# E17-04_BSPD.net
KiCad netlist of a schematic drawn in Altium Designer
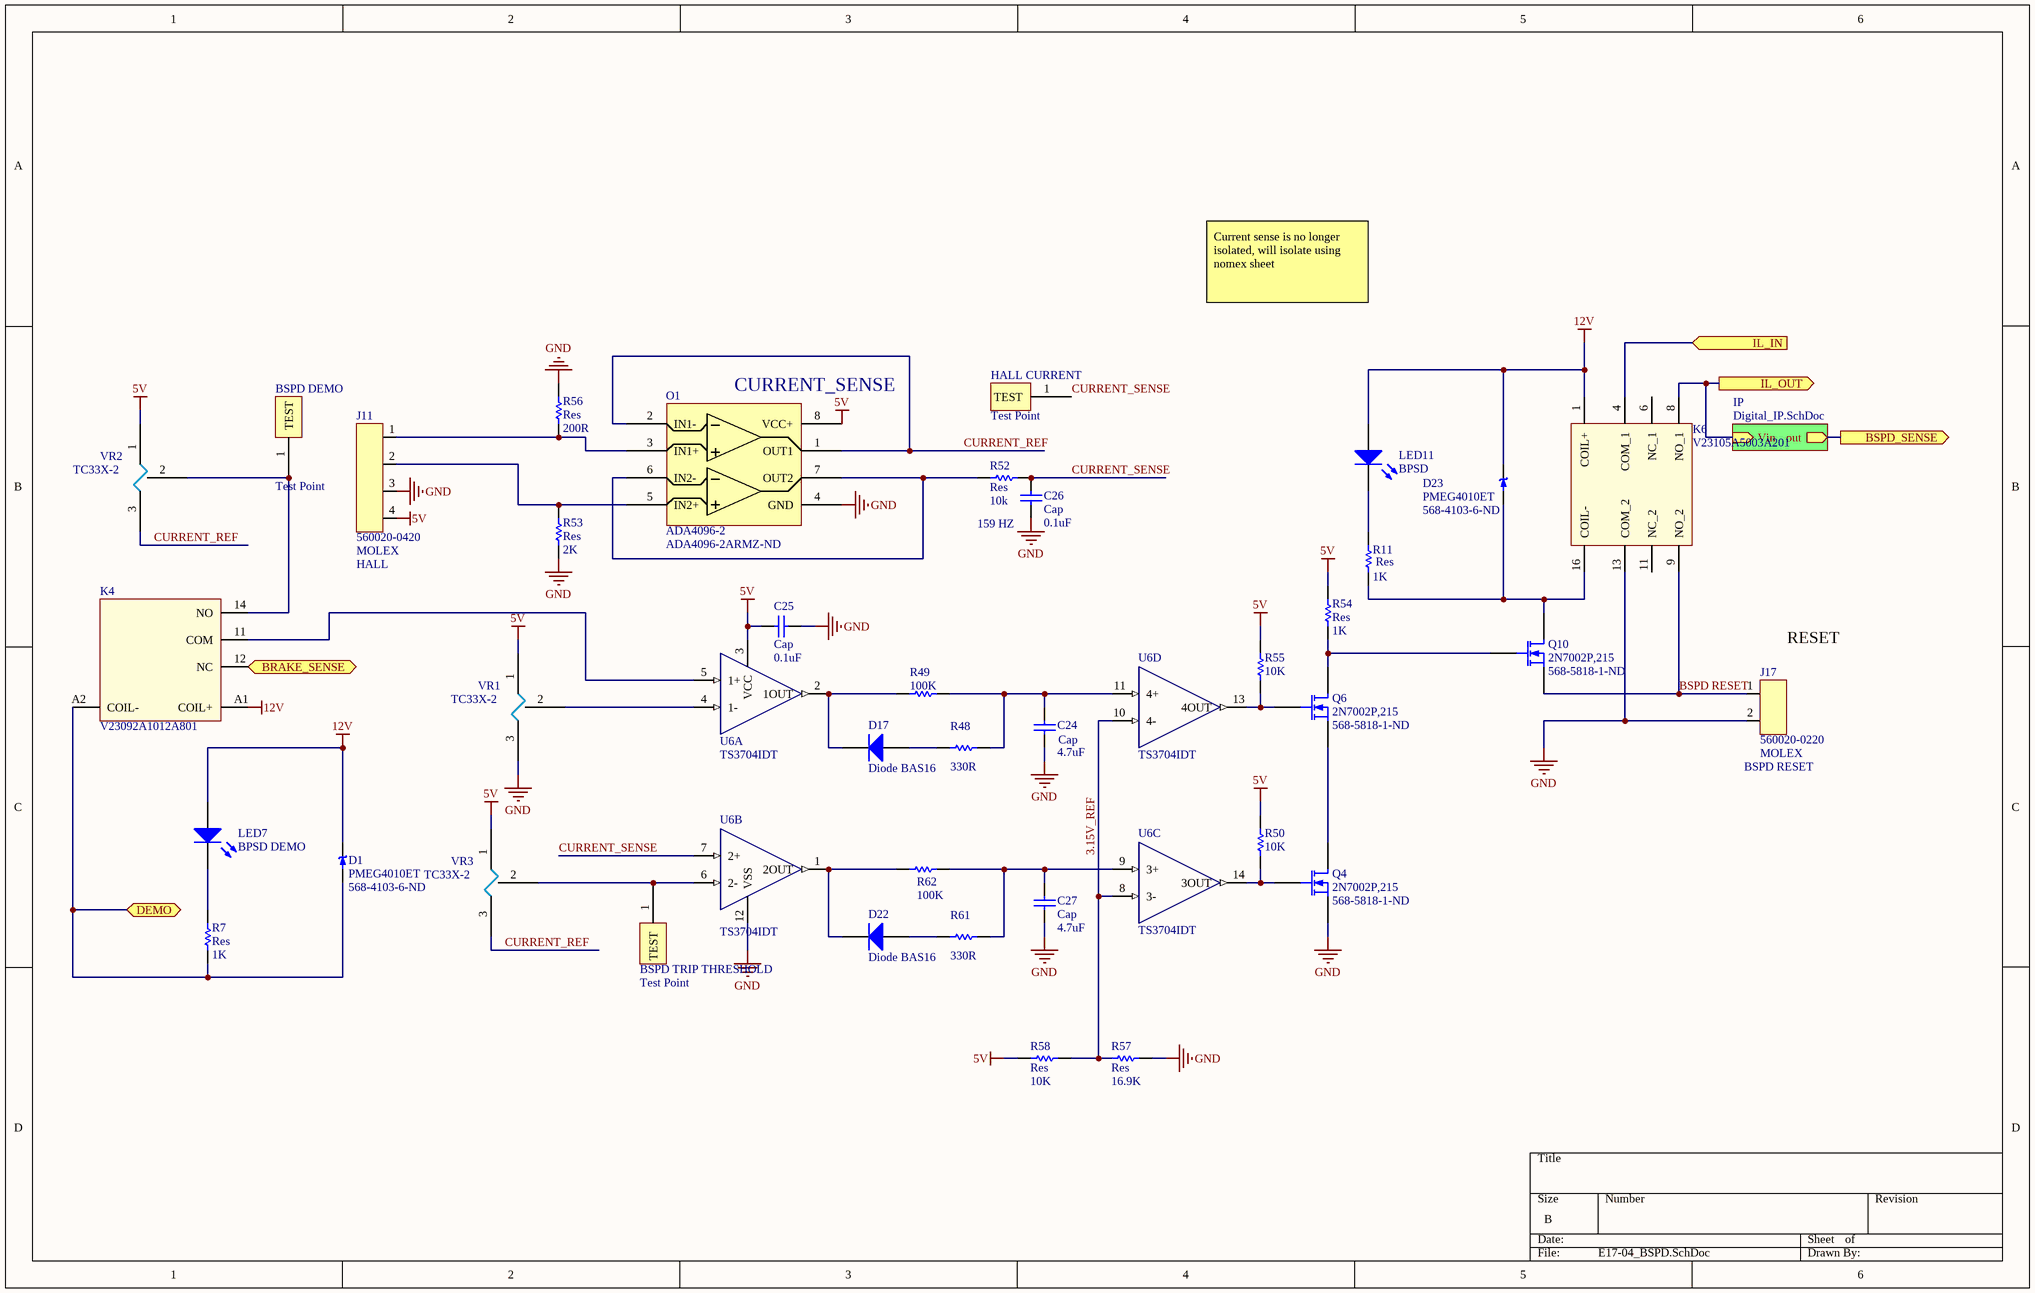
[diagram p0: E17-04_BSPD.SchDoc]

(export (version "E")
  (design (tool "Eeschema 10.0.6"))
  (components
    (comp (ref "BSPD DEMO")
      (value "Test Point")
      (footprint "TEST POINT 5000K")
      (description "5000-5004, 5015-5019 Keystone Electronics")
      (libsource (lib "") (part "Test Point_1"))
    )
    (comp (ref "BSPD TRIP THRESHOLD")
      (value "Test Point")
      (footprint "TEST POINT 5000K")
      (description "5000-5004, 5015-5019 Keystone Electronics")
      (libsource (lib "Mechanical Devices") (part "Test Point"))
    )
    (comp (ref "C24")
      (value "Cap")
      (footprint "C0805")
      (description "Capacitor")
      (fields (field (name "ALTIUM_VALUE") "4.7uF") (field (name "PUBLISHER") "Altium Limited"))
      (libsource (lib "Capacitors") (part "Cap"))
    )
    (comp (ref "C25")
      (value "Cap")
      (footprint "C0805")
      (description "Capacitor")
      (fields (field (name "ALTIUM_VALUE") "0.1uF") (field (name "PUBLISHER") "Altium Limited"))
      (libsource (lib "Capacitors") (part "Cap"))
    )
    (comp (ref "C26")
      (value "Cap")
      (footprint "C0805")
      (description "Capacitor")
      (fields (field (name "ALTIUM_VALUE") "0.1uF") (field (name "PUBLISHER") "Altium Limited"))
      (libsource (lib "Capacitors") (part "Cap"))
    )
    (comp (ref "C27")
      (value "Cap")
      (footprint "C0805")
      (description "Capacitor")
      (fields (field (name "ALTIUM_VALUE") "4.7uF") (field (name "PUBLISHER") "Altium Limited"))
      (libsource (lib "Capacitors") (part "Cap"))
    )
    (comp (ref "D1")
      (value "PMEG4010ET")
      (footprint "SOT23-3")
      (description "SCHOTTKY RECT 40V 1A SOT-23")
      (fields (field (name "SUPPLIER PART NUMBER 1") "568-4103-6-ND"))
      (libsource (lib "Diodes") (part "PMEG4010ET"))
    )
    (comp (ref "D17")
      (value "Diode BAS16")
      (footprint "SOT-23_N")
      (description "Silicon Switching Diode for High-Speed Switching")
      (fields (field (name "PUBLISHER") "Altium Limited"))
      (libsource (lib "Miscellaneous Devices") (part "Diode BAS16"))
    )
    (comp (ref "D22")
      (value "Diode BAS16")
      (footprint "SOT-23_N")
      (description "Silicon Switching Diode for High-Speed Switching")
      (fields (field (name "PUBLISHER") "Altium Limited"))
      (libsource (lib "Miscellaneous Devices") (part "Diode BAS16"))
    )
    (comp (ref "D23")
      (value "PMEG4010ET")
      (footprint "SOT23-3")
      (description "SCHOTTKY RECT 40V 1A SOT-23")
      (fields (field (name "SUPPLIER PART NUMBER 1") "568-4103-6-ND"))
      (libsource (lib "Diodes") (part "PMEG4010ET"))
    )
    (comp (ref "HALL CURRENT")
      (value "Test Point")
      (footprint "TEST POINT 5000K")
      (description "5000-5004, 5015-5019 Keystone Electronics")
      (libsource (lib "") (part "Test Point_2"))
    )
    (comp (ref "J11")
      (value "HALL")
      (footprint "MOLEX_DURACLIK_4 NAT VERT")
      (description "MOLEX DURACLIK 4-PIN VERT NAT")
      (fields
        (field (name "VOLTAGE") "125")
        (field (name "MPN") "560020-0420")
        (field (name "MANUFACTURER") "MOLEX")
        (field (name "COMMENT_1") "HALL")
      )
      (libsource (lib "Molex_DuraClik") (part "560020-0420"))
    )
    (comp (ref "J17")
      (value "BSPD RESET")
      (footprint "MOLEX_DURACLIK_2 NAT VERT")
      (description "MOLEX DURACLIK 2-PIN VERT NAT")
      (fields
        (field (name "VOLTAGE") "125")
        (field (name "MPN") "560020-0220")
        (field (name "MANUFACTURER") "MOLEX")
      )
      (libsource (lib "Molex_DuraClik") (part "560020-0220"))
    )
    (comp (ref "K4")
      (value "V23092A1012A801")
      (footprint "SCHRACK")
      (description "12V slim SPDT Relay")
      (fields (field (name "MFG") "TE") (field (name "MFG_PN") "V23092A1012A801"))
      (libsource (lib "Relays") (part "V23092A1012A801"))
    )
    (comp (ref "K6")
      (value "K_V23105A5003A201")
      (footprint "K_V23105A5003A201")
      (description "RELAY DPDT 12V/12.5mA, 220V/3A")
      (fields (field (name "MFG") "TE") (field (name "MFG_PN") "V23105A5003A201"))
      (libsource (lib "Relays") (part "K_V23105A5003A201"))
    )
    (comp (ref "LED7")
      (value "BPSD DEMO")
      (footprint "155124VS73200")
      (description "Right Angle SMD Green 2V")
      (fields
        (field (name "MANUFACTURER") "Wurth Electronics Inc")
        (field (name "MANUFACTURER PART NUMBER") "155124VS73200")
      )
      (libsource (lib "LEDs") (part "155124VS73200"))
    )
    (comp (ref "LED11")
      (value "BPSD")
      (footprint "155124VS73200")
      (description "Right Angle SMD Green 2V")
      (fields
        (field (name "MANUFACTURER") "Wurth Electronics Inc")
        (field (name "MANUFACTURER PART NUMBER") "155124VS73200")
      )
      (libsource (lib "LEDs") (part "155124VS73200"))
    )
    (comp (ref "O1")
      (value "ADA4096-2")
      (footprint "TSSOP8")
      (description "2 Op-Amps, 8-TSSOP, 32V Overvoltage Protection")
      (fields (field (name "SUPPLIER PART NUMBER 1") "ADA4096-2ARMZ-ND"))
      (libsource (lib "Operational Amplifiers") (part "ADA4096-2"))
    )
    (comp (ref "Q4")
      (value "2N7002P,215")
      (footprint "SOT23-3")
      (description "N-Channel Enhancement Mode Vertical DMOS FET")
      (fields (field (name "SUPPLIER PART NUMBER 1") "568-5818-1-ND"))
      (libsource (lib "Transistors") (part "2N7002P,215"))
    )
    (comp (ref "Q6")
      (value "2N7002P,215")
      (footprint "SOT23-3")
      (description "N-Channel Enhancement Mode Vertical DMOS FET")
      (fields (field (name "SUPPLIER PART NUMBER 1") "568-5818-1-ND"))
      (libsource (lib "Transistors") (part "2N7002P,215"))
    )
    (comp (ref "Q10")
      (value "2N7002P,215")
      (footprint "SOT23-3")
      (description "N-Channel Enhancement Mode Vertical DMOS FET")
      (fields (field (name "SUPPLIER PART NUMBER 1") "568-5818-1-ND"))
      (libsource (lib "Transistors") (part "2N7002P,215"))
    )
    (comp (ref "R7")
      (value "Res")
      (footprint "2012[0805]")
      (description "Surface Mount Resistor")
      (fields (field (name "ALTIUM_VALUE") "1K") (field (name "PUBLISHER") "Altium Limited"))
      (libsource (lib "Resistors") (part "Res"))
    )
    (comp (ref "R11")
      (value "Res")
      (footprint "2012[0805]")
      (description "Surface Mount Resistor")
      (fields (field (name "ALTIUM_VALUE") "1K") (field (name "PUBLISHER") "Altium Limited"))
      (libsource (lib "Resistors") (part "Res"))
    )
    (comp (ref "R48")
      (value "330R")
      (footprint "2012[0805]")
      (description "Surface Mount Resistor")
      (fields (field (name "Comment") "Res") (field (name "PUBLISHER") "Altium Limited"))
      (libsource (lib "Resistors") (part "Res"))
    )
    (comp (ref "R49")
      (value "100K")
      (footprint "2012[0805]")
      (description "Surface Mount Resistor")
      (fields (field (name "Comment") "Res") (field (name "PUBLISHER") "Altium Limited"))
      (libsource (lib "Resistors") (part "Res"))
    )
    (comp (ref "R50")
      (value "10K")
      (footprint "2012[0805]")
      (description "Surface Mount Resistor")
      (fields (field (name "Comment") "Res") (field (name "PUBLISHER") "Altium Limited"))
      (libsource (lib "Resistors") (part "Res"))
    )
    (comp (ref "R52")
      (value "Res")
      (footprint "2012[0805]")
      (description "Surface Mount Resistor")
      (fields (field (name "ALTIUM_VALUE") "10k") (field (name "PUBLISHER") "Altium Limited"))
      (libsource (lib "Resistors") (part "Res"))
    )
    (comp (ref "R53")
      (value "Res")
      (footprint "2012[0805]")
      (description "Surface Mount Resistor")
      (fields (field (name "ALTIUM_VALUE") "2K") (field (name "PUBLISHER") "Altium Limited"))
      (libsource (lib "Resistors") (part "Res"))
    )
    (comp (ref "R54")
      (value "Res")
      (footprint "2012[0805]")
      (description "Surface Mount Resistor")
      (fields (field (name "ALTIUM_VALUE") "1K") (field (name "PUBLISHER") "Altium Limited"))
      (libsource (lib "Resistors") (part "Res"))
    )
    (comp (ref "R55")
      (value "10K")
      (footprint "2012[0805]")
      (description "Surface Mount Resistor")
      (fields (field (name "Comment") "Res") (field (name "PUBLISHER") "Altium Limited"))
      (libsource (lib "Resistors") (part "Res"))
    )
    (comp (ref "R56")
      (value "Res")
      (footprint "2012[0805]")
      (description "Surface Mount Resistor")
      (fields (field (name "ALTIUM_VALUE") "200R") (field (name "PUBLISHER") "Altium Limited"))
      (libsource (lib "Resistors") (part "Res"))
    )
    (comp (ref "R57")
      (value "Res")
      (footprint "2012[0805]")
      (description "Surface Mount Resistor")
      (fields (field (name "ALTIUM_VALUE") "16.9K") (field (name "PUBLISHER") "Altium Limited"))
      (libsource (lib "Resistors") (part "Res"))
    )
    (comp (ref "R58")
      (value "Res")
      (footprint "2012[0805]")
      (description "Surface Mount Resistor")
      (fields (field (name "ALTIUM_VALUE") "10K") (field (name "PUBLISHER") "Altium Limited"))
      (libsource (lib "Resistors") (part "Res"))
    )
    (comp (ref "R61")
      (value "330R")
      (footprint "2012[0805]")
      (description "Surface Mount Resistor")
      (fields (field (name "Comment") "Res") (field (name "PUBLISHER") "Altium Limited"))
      (libsource (lib "Resistors") (part "Res"))
    )
    (comp (ref "R62")
      (value "100K")
      (footprint "2012[0805]")
      (description "Surface Mount Resistor")
      (fields (field (name "Comment") "Res") (field (name "PUBLISHER") "Altium Limited"))
      (libsource (lib "Resistors") (part "Res"))
    )
    (comp (ref "U6")
      (value "U_TS3704IDT")
      (footprint "14-SOIC")
      (description "QUAD COMPARATOR 14-SOIC PUSH-PULL")
      (fields (field (name "MFG") "STMicroelectronics") (field (name "MFG_PN") "TS3704IDT"))
      (libsource (lib "Operational_Amplifiers") (part "U_TS3704IDT"))
    )
    (comp (ref "VR1") (value "TC33X-2") (footprint "TC33X-2") (libsource (lib "Resistors") (part "TC33X-2")))
    (comp (ref "VR2") (value "TC33X-2") (footprint "TC33X-2") (libsource (lib "Resistors") (part "TC33X-2")))
    (comp (ref "VR3") (value "TC33X-2") (footprint "TC33X-2") (libsource (lib "Resistors") (part "TC33X-2")))
  )
  (nets
    (net (code "1") (name "/3.15V_REF") (class "Default")
      (node (ref "R57") (pin "2") (pinfunction "2_2") (pintype "passive"))
      (node (ref "R58") (pin "1") (pinfunction "1_1") (pintype "passive"))
      (node (ref "U6") (pin "10") (pinfunction "4-_10") (pintype "input"))
      (node (ref "U6") (pin "8") (pinfunction "3-_8") (pintype "input"))
    )
    (net (code "2") (name "/BRAKE_SENSE") (class "Default")
      (node (ref "K4") (pin "12") (pinfunction "NC_12") (pintype "passive"))
    )
    (net (code "3") (name "/BSPD RESET") (class "Default")
      (node (ref "J17") (pin "1") (pinfunction "1_1") (pintype "passive"))
      (node (ref "K6") (pin "9") (pinfunction "NO_2_9") (pintype "passive"))
      (node (ref "Q10") (pin "2") (pinfunction "S_2") (pintype "passive"))
    )
    (net (code "5") (name "/CURRENT_REF") (class "Default")
      (node (ref "O1") (pin "1") (pinfunction "OUT1_1") (pintype "passive"))
      (node (ref "O1") (pin "2") (pinfunction "IN1-_2") (pintype "passive"))
      (node (ref "VR2") (pin "3") (pinfunction "3_3") (pintype "passive"))
      (node (ref "VR3") (pin "3") (pinfunction "3_3") (pintype "passive"))
    )
    (net (code "6") (name "/CURRENT_SENSE") (class "Default")
      (node (ref "C26") (pin "2") (pinfunction "2_2") (pintype "passive"))
      (node (ref "HALL CURRENT") (pin "1") (pinfunction "TEST_1") (pintype "passive"))
      (node (ref "R52") (pin "1") (pinfunction "1_1") (pintype "passive"))
      (node (ref "U6") (pin "7") (pinfunction "2+_7") (pintype "input"))
    )
    (net (code "7") (name "/DEMO") (class "Default")
      (node (ref "D1") (pin "1") (pinfunction "1_1") (pintype "passive"))
      (node (ref "K4") (pin "A2") (pinfunction "COIL-_A2") (pintype "passive"))
      (node (ref "R7") (pin "1") (pinfunction "1_1") (pintype "passive"))
    )
    (net (code "8") (name "/IL_IN") (class "Default")
      (node (ref "K6") (pin "4") (pinfunction "COM_1_4") (pintype "passive"))
    )
    (net (code "9") (name "/IL_OUT") (class "Default")
      (node (ref "K6") (pin "8") (pinfunction "NO_1_8") (pintype "passive"))
    )
    (net (code "10") (name "5V") (class "Default")
      (node (ref "C25") (pin "2") (pinfunction "2_2") (pintype "passive"))
      (node (ref "J11") (pin "4") (pinfunction "4_4") (pintype "passive"))
      (node (ref "O1") (pin "8") (pinfunction "VCC+_8") (pintype "passive"))
      (node (ref "R50") (pin "2") (pinfunction "2_2") (pintype "passive"))
      (node (ref "R54") (pin "1") (pinfunction "1_1") (pintype "passive"))
      (node (ref "R55") (pin "2") (pinfunction "2_2") (pintype "passive"))
      (node (ref "R58") (pin "2") (pinfunction "2_2") (pintype "passive"))
      (node (ref "U6") (pin "3") (pinfunction "VCC_3") (pintype "power_in"))
      (node (ref "VR1") (pin "1") (pinfunction "1_1") (pintype "passive"))
      (node (ref "VR2") (pin "1") (pinfunction "1_1") (pintype "passive"))
      (node (ref "VR3") (pin "1") (pinfunction "1_1") (pintype "passive"))
    )
    (net (code "11") (name "12V") (class "Default")
      (node (ref "D1") (pin "3") (pinfunction "3_3") (pintype "passive"))
      (node (ref "D23") (pin "3") (pinfunction "3_3") (pintype "passive"))
      (node (ref "K4") (pin "A1") (pinfunction "COIL+_A1") (pintype "passive"))
      (node (ref "K6") (pin "1") (pinfunction "COIL+_1") (pintype "passive"))
      (node (ref "LED11") (pin "2") (pinfunction "2_2") (pintype "passive"))
      (node (ref "LED7") (pin "2") (pinfunction "2_2") (pintype "passive"))
    )
    (net (code "12") (name "GND") (class "Default")
      (node (ref "C24") (pin "1") (pinfunction "1_1") (pintype "passive"))
      (node (ref "C25") (pin "1") (pinfunction "1_1") (pintype "passive"))
      (node (ref "C26") (pin "1") (pinfunction "1_1") (pintype "passive"))
      (node (ref "C27") (pin "1") (pinfunction "1_1") (pintype "passive"))
      (node (ref "J11") (pin "3") (pinfunction "3_3") (pintype "passive"))
      (node (ref "J17") (pin "2") (pinfunction "2_2") (pintype "passive"))
      (node (ref "K6") (pin "13") (pinfunction "COM_2_13") (pintype "passive"))
      (node (ref "O1") (pin "4") (pinfunction "GND_4") (pintype "passive"))
      (node (ref "Q4") (pin "2") (pinfunction "S_2") (pintype "passive"))
      (node (ref "R53") (pin "1") (pinfunction "1_1") (pintype "passive"))
      (node (ref "R56") (pin "1") (pinfunction "1_1") (pintype "passive"))
      (node (ref "R57") (pin "1") (pinfunction "1_1") (pintype "passive"))
      (node (ref "U6") (pin "12") (pinfunction "VSS_12") (pintype "power_in"))
      (node (ref "VR1") (pin "3") (pinfunction "3_3") (pintype "passive"))
    )
    (net (code "13") (name "Net-(BSPD DEMO-TEST)") (class "Default")
      (node (ref "BSPD DEMO") (pin "1") (pinfunction "TEST_1") (pintype "passive"))
      (node (ref "K4") (pin "14") (pinfunction "NO_14") (pintype "passive"))
      (node (ref "VR2") (pin "2") (pinfunction "2_2") (pintype "passive"))
    )
    (net (code "14") (name "Net-(BSPD TRIP THRESHOLD-TEST)") (class "Default")
      (node (ref "BSPD TRIP THRESHOLD") (pin "1") (pinfunction "TEST_1") (pintype "passive"))
      (node (ref "U6") (pin "6") (pinfunction "2-_6") (pintype "input"))
      (node (ref "VR3") (pin "2") (pinfunction "2_2") (pintype "passive"))
    )
    (net (code "15") (name "Net-(D17-A)") (class "Default")
      (node (ref "D17") (pin "1") (pinfunction "A_1") (pintype "passive"))
      (node (ref "R48") (pin "1") (pinfunction "1_1") (pintype "passive"))
    )
    (net (code "16") (name "Net-(D17-K)") (class "Default")
      (node (ref "D17") (pin "3") (pinfunction "K_3") (pintype "passive"))
      (node (ref "R49") (pin "1") (pinfunction "1_1") (pintype "passive"))
      (node (ref "U6") (pin "2") (pinfunction "1OUT_2") (pintype "output"))
    )
    (net (code "17") (name "Net-(D22-A)") (class "Default")
      (node (ref "D22") (pin "1") (pinfunction "A_1") (pintype "passive"))
      (node (ref "R61") (pin "1") (pinfunction "1_1") (pintype "passive"))
    )
    (net (code "18") (name "Net-(D22-K)") (class "Default")
      (node (ref "D22") (pin "3") (pinfunction "K_3") (pintype "passive"))
      (node (ref "R62") (pin "1") (pinfunction "1_1") (pintype "passive"))
      (node (ref "U6") (pin "1") (pinfunction "2OUT_1") (pintype "output"))
    )
    (net (code "19") (name "Net-(K4-COM)") (class "Default")
      (node (ref "K4") (pin "11") (pinfunction "COM_11") (pintype "passive"))
      (node (ref "U6") (pin "5") (pinfunction "1+_5") (pintype "input"))
    )
    (net (code "20") (name "Net-(K6-COIL-)") (class "Default")
      (node (ref "D23") (pin "1") (pinfunction "1_1") (pintype "passive"))
      (node (ref "K6") (pin "16") (pinfunction "COIL-_16") (pintype "passive"))
      (node (ref "Q10") (pin "3") (pinfunction "D_3") (pintype "passive"))
      (node (ref "R11") (pin "1") (pinfunction "1_1") (pintype "passive"))
    )
    (net (code "21") (name "Net-(LED7-Pad1)") (class "Default")
      (node (ref "LED7") (pin "1") (pinfunction "1_1") (pintype "passive"))
      (node (ref "R7") (pin "2") (pinfunction "2_2") (pintype "passive"))
    )
    (net (code "22") (name "Net-(LED11-Pad1)") (class "Default")
      (node (ref "LED11") (pin "1") (pinfunction "1_1") (pintype "passive"))
      (node (ref "R11") (pin "2") (pinfunction "2_2") (pintype "passive"))
    )
    (net (code "23") (name "Net-(O1-IN1+)") (class "Default")
      (node (ref "J11") (pin "1") (pinfunction "1_1") (pintype "passive"))
      (node (ref "O1") (pin "3") (pinfunction "IN1+_3") (pintype "passive"))
      (node (ref "R56") (pin "2") (pinfunction "2_2") (pintype "passive"))
    )
    (net (code "24") (name "Net-(O1-IN2+)") (class "Default")
      (node (ref "J11") (pin "2") (pinfunction "2_2") (pintype "passive"))
      (node (ref "O1") (pin "5") (pinfunction "IN2+_5") (pintype "passive"))
      (node (ref "R53") (pin "2") (pinfunction "2_2") (pintype "passive"))
    )
    (net (code "25") (name "Net-(O1-IN2-)") (class "Default")
      (node (ref "O1") (pin "6") (pinfunction "IN2-_6") (pintype "passive"))
      (node (ref "O1") (pin "7") (pinfunction "OUT2_7") (pintype "passive"))
      (node (ref "R52") (pin "2") (pinfunction "2_2") (pintype "passive"))
    )
    (net (code "26") (name "Net-(Q4-D)") (class "Default")
      (node (ref "Q4") (pin "3") (pinfunction "D_3") (pintype "passive"))
      (node (ref "Q6") (pin "2") (pinfunction "S_2") (pintype "passive"))
    )
    (net (code "27") (name "Net-(Q4-G)") (class "Default")
      (node (ref "Q4") (pin "1") (pinfunction "G_1") (pintype "passive"))
      (node (ref "R50") (pin "1") (pinfunction "1_1") (pintype "passive"))
      (node (ref "U6") (pin "14") (pinfunction "3OUT_14") (pintype "output"))
    )
    (net (code "28") (name "Net-(Q6-G)") (class "Default")
      (node (ref "Q6") (pin "1") (pinfunction "G_1") (pintype "passive"))
      (node (ref "R55") (pin "1") (pinfunction "1_1") (pintype "passive"))
      (node (ref "U6") (pin "13") (pinfunction "4OUT_13") (pintype "output"))
    )
    (net (code "29") (name "Net-(Q10-G)") (class "Default")
      (node (ref "Q10") (pin "1") (pinfunction "G_1") (pintype "passive"))
      (node (ref "Q6") (pin "3") (pinfunction "D_3") (pintype "passive"))
      (node (ref "R54") (pin "2") (pinfunction "2_2") (pintype "passive"))
    )
    (net (code "30") (name "Net-(U6A-1-)") (class "Default")
      (node (ref "U6") (pin "4") (pinfunction "1-_4") (pintype "input"))
      (node (ref "VR1") (pin "2") (pinfunction "2_2") (pintype "passive"))
    )
    (net (code "31") (name "Net-(U6C-3+)") (class "Default")
      (node (ref "C27") (pin "2") (pinfunction "2_2") (pintype "passive"))
      (node (ref "R61") (pin "2") (pinfunction "2_2") (pintype "passive"))
      (node (ref "R62") (pin "2") (pinfunction "2_2") (pintype "passive"))
      (node (ref "U6") (pin "9") (pinfunction "3+_9") (pintype "input"))
    )
    (net (code "32") (name "Net-(U6D-4+)") (class "Default")
      (node (ref "C24") (pin "2") (pinfunction "2_2") (pintype "passive"))
      (node (ref "R48") (pin "2") (pinfunction "2_2") (pintype "passive"))
      (node (ref "R49") (pin "2") (pinfunction "2_2") (pintype "passive"))
      (node (ref "U6") (pin "11") (pinfunction "4+_11") (pintype "input"))
    )
    (net (code "33") (name "unconnected-(K6-NC_1-Pad6)") (class "Default")
      (node (ref "K6") (pin "6") (pinfunction "NC_1_6") (pintype "passive"))
    )
    (net (code "34") (name "unconnected-(K6-NC_2-Pad11)") (class "Default")
      (node (ref "K6") (pin "11") (pinfunction "NC_2_11") (pintype "passive"))
    )
  )
)
